# ProProject_RJ45_2023-11-09.net
KiCad netlist of a schematic drawn in EasyEDA Pro
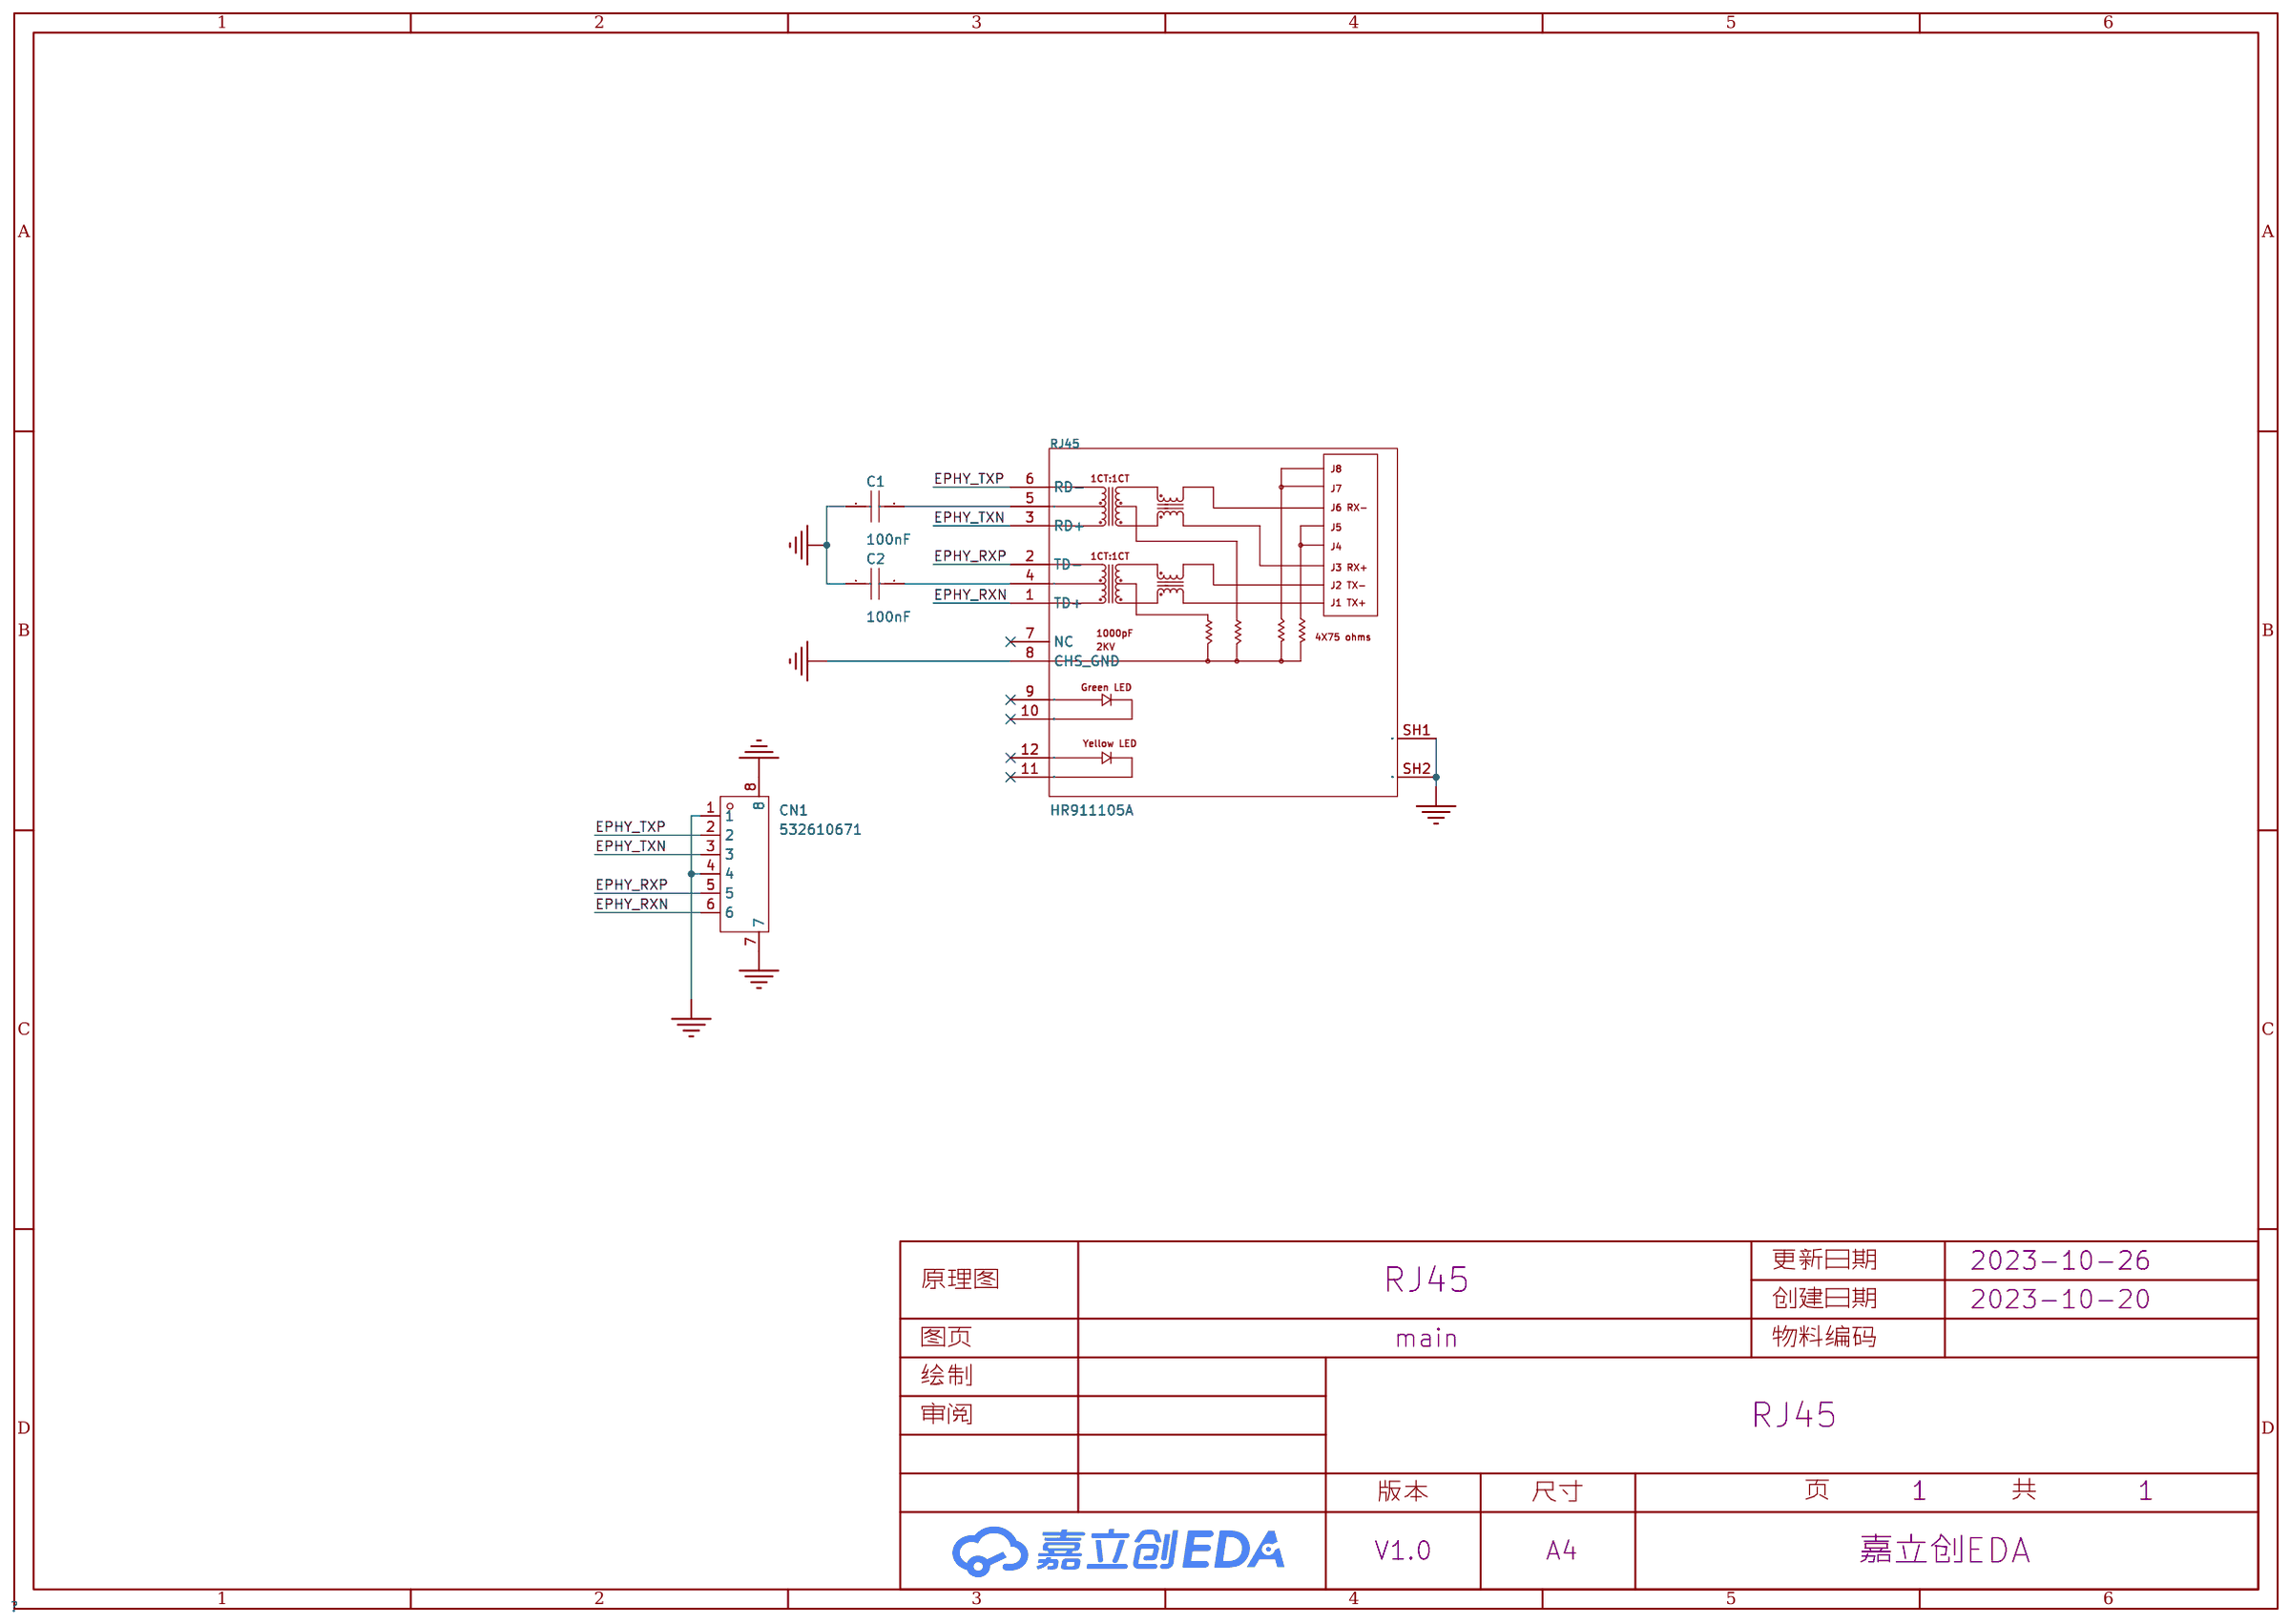
[diagram p0: schematic sheet]

(export (version "E")
  (design (tool "Eeschema 10.0.6"))
  (components
    (comp (ref "C1")
      (value "100nF")
      (footprint "easyedapro:C0402")
      (description "容值:100nF;精度:±10%;额定电压:16V;材质(温度系数):X7R;")
      (fields
        (field (name "Manufacturer Part") "CL05B104KO5NNNC")
        (field (name "Manufacturer") "SAMSUNG(三星)")
      )
      (libsource (lib "easyedapro") (part "CL05B104KO5NNNC"))
    )
    (comp (ref "C2")
      (value "100nF")
      (footprint "easyedapro:C0402")
      (description "容值:100nF;精度:±10%;额定电压:16V;材质(温度系数):X7R;")
      (fields
        (field (name "Manufacturer Part") "CL05B104KO5NNNC")
        (field (name "Manufacturer") "SAMSUNG(三星)")
      )
      (libsource (lib "easyedapro") (part "CL05B104KO5NNNC"))
    )
    (comp (ref "CN1")
      (value "532610671")
      (footprint "easyedapro:CONN-SMD_6P-P1.25_53261-0671")
      (description "参考系列:-;间距:1.25mm;插针结构:1x6P;排数:1;每排PIN数:6;行距:-;安装方式:-;触头材质:青铜;")
      (fields (field (name "Manufacturer") "MOLEX"))
      (libsource (lib "easyedapro") (part "53261-0671"))
    )
    (comp (ref "RJ45")
      (value "HR911105A")
      (footprint "easyedapro:RJ45-TH_HR911105A")
      (description "连接器类型:RJ插座;USOC代码:RJ45;端口数量:1;等级:-;屏蔽:-;LED:带LED;")
      (fields (field (name "Manufacturer") "HANRUN(汉仁)"))
      (libsource (lib "easyedapro") (part "HR911105A_C12074"))
    )
  )
  (nets
    (net (code "1") (name "/EPHY_RXN") (class "Default")
      (node (ref "CN1") (pin "6") (pinfunction "6_6") (pintype "input"))
      (node (ref "RJ45") (pin "1") (pinfunction "TD+_1") (pintype "input"))
    )
    (net (code "2") (name "/EPHY_RXP") (class "Default")
      (node (ref "CN1") (pin "5") (pinfunction "5_5") (pintype "input"))
      (node (ref "RJ45") (pin "2") (pinfunction "TD-_2") (pintype "input"))
    )
    (net (code "3") (name "/EPHY_TXN") (class "Default")
      (node (ref "CN1") (pin "3") (pinfunction "3_3") (pintype "input"))
      (node (ref "RJ45") (pin "3") (pinfunction "RD+_3") (pintype "input"))
    )
    (net (code "4") (name "/EPHY_TXP") (class "Default")
      (node (ref "CN1") (pin "2") (pinfunction "2_2") (pintype "input"))
      (node (ref "RJ45") (pin "6") (pinfunction "RD-_6") (pintype "input"))
    )
    (net (code "5") (name "GND") (class "Default")
      (node (ref "C1") (pin "1") (pinfunction "1_1") (pintype "input"))
      (node (ref "C2") (pin "1") (pinfunction "1_1") (pintype "input"))
      (node (ref "CN1") (pin "1") (pinfunction "1_1") (pintype "input"))
      (node (ref "CN1") (pin "4") (pinfunction "4_4") (pintype "input"))
      (node (ref "CN1") (pin "7") (pinfunction "7_7") (pintype "input"))
      (node (ref "CN1") (pin "8") (pinfunction "8_8") (pintype "input"))
      (node (ref "RJ45") (pin "8") (pinfunction "CHS_GND_8") (pintype "input"))
      (node (ref "RJ45") (pin "SH1") (pinfunction "SH1_SH1") (pintype "input"))
      (node (ref "RJ45") (pin "SH2") (pinfunction "SH2_SH2") (pintype "input"))
    )
    (net (code "6") (name "Net-(C1-Pad2)") (class "Default")
      (node (ref "C1") (pin "2") (pinfunction "2_2") (pintype "input"))
      (node (ref "RJ45") (pin "5") (pinfunction "5_5") (pintype "input"))
    )
    (net (code "7") (name "Net-(C2-Pad2)") (class "Default")
      (node (ref "C2") (pin "2") (pinfunction "2_2") (pintype "input"))
      (node (ref "RJ45") (pin "4") (pinfunction "4_4") (pintype "input"))
    )
    (net (code "8") (name "unconnected-(RJ45-NC-Pad7)") (class "Default")
      (node (ref "RJ45") (pin "7") (pinfunction "NC_7") (pintype "input+no_connect"))
    )
    (net (code "9") (name "unconnected-(RJ45-Pad9)") (class "Default")
      (node (ref "RJ45") (pin "9") (pinfunction "9_9") (pintype "input+no_connect"))
    )
    (net (code "10") (name "unconnected-(RJ45-Pad10)") (class "Default")
      (node (ref "RJ45") (pin "10") (pinfunction "10_10") (pintype "input+no_connect"))
    )
    (net (code "11") (name "unconnected-(RJ45-Pad11)") (class "Default")
      (node (ref "RJ45") (pin "11") (pinfunction "11_11") (pintype "input+no_connect"))
    )
    (net (code "12") (name "unconnected-(RJ45-Pad12)") (class "Default")
      (node (ref "RJ45") (pin "12") (pinfunction "12_12") (pintype "input+no_connect"))
    )
  )
)
